# AnyFC_Final.net
KiCad netlist of a schematic drawn in EAGLE
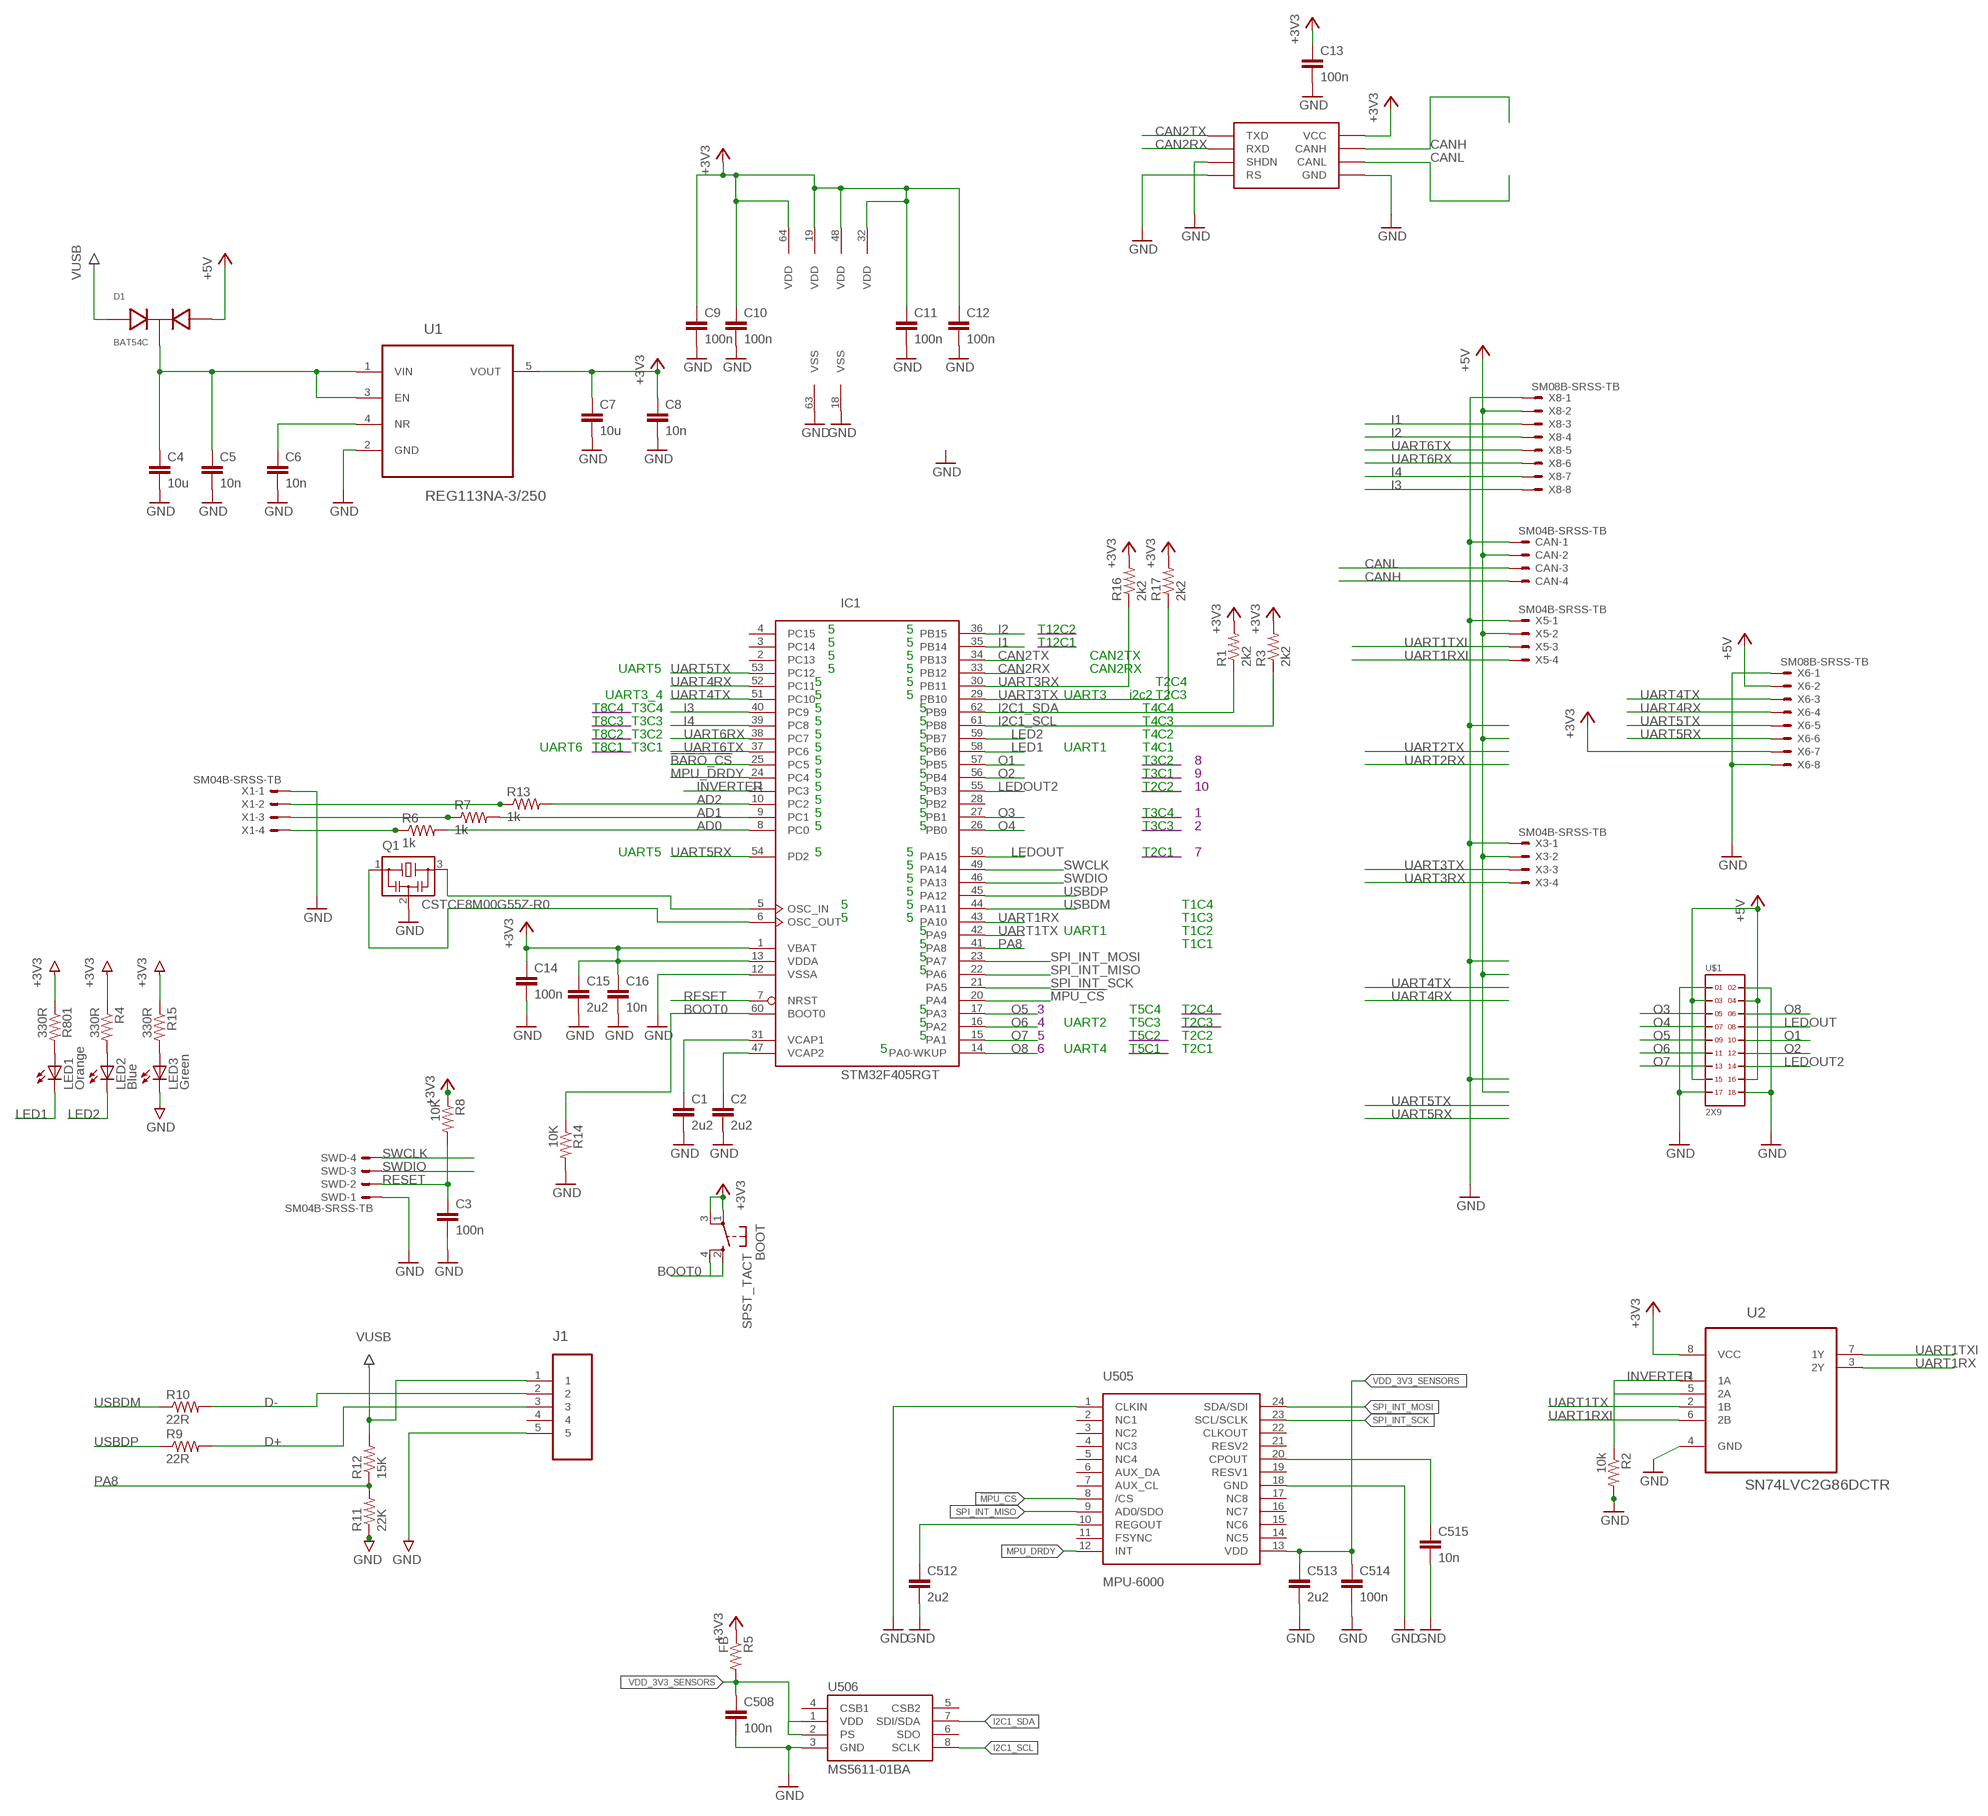
[diagram p0: schematic, sheet 1]

(export (version "E")
  (design (tool "Eeschema 10.0.6"))
  (components
    (comp (ref "BOOT")
      (value "SPST_TACT")
      (footprint "eagle-import:EVQ-PU")
      (libsource (lib "eagle-import") (part "SPST_TACT"))
    )
    (comp (ref "C1")
      (value "2u2")
      (footprint "eagle-import:0603-CAP")
      (fields (field (name "PARTNO") "C1608X6S1C225K080AC"))
      (libsource (lib "eagle-import") (part "CAP0603"))
    )
    (comp (ref "C2")
      (value "2u2")
      (footprint "eagle-import:0603-CAP")
      (fields (field (name "PARTNO") "C1608X6S1C225K080AC"))
      (libsource (lib "eagle-import") (part "CAP0603"))
    )
    (comp (ref "C3")
      (value "100n")
      (footprint "eagle-import:0402-CAP")
      (fields (field (name "PARTNO") "C1608X6S1C225K080AC"))
      (libsource (lib "eagle-import") (part "CAP0402"))
    )
    (comp (ref "C4")
      (value "10u")
      (footprint "eagle-import:0805-CAP")
      (fields (field (name "PARTNO") "C1608X6S1C225K080AC"))
      (libsource (lib "eagle-import") (part "CAP0805"))
    )
    (comp (ref "C5")
      (value "10n")
      (footprint "eagle-import:0402-CAP")
      (fields (field (name "PARTNO") "C1608X6S1C225K080AC"))
      (libsource (lib "eagle-import") (part "CAP0402"))
    )
    (comp (ref "C6")
      (value "10n")
      (footprint "eagle-import:0402-CAP")
      (fields (field (name "PARTNO") "C1608X6S1C225K080AC"))
      (libsource (lib "eagle-import") (part "CAP0402"))
    )
    (comp (ref "C7")
      (value "10u")
      (footprint "eagle-import:0805-CAP")
      (fields (field (name "PARTNO") "C1608X6S1C225K080AC"))
      (libsource (lib "eagle-import") (part "CAP0805"))
    )
    (comp (ref "C8")
      (value "10n")
      (footprint "eagle-import:0402-CAP")
      (fields (field (name "PARTNO") "C1608X6S1C225K080AC"))
      (libsource (lib "eagle-import") (part "CAP0402"))
    )
    (comp (ref "C9")
      (value "100n")
      (footprint "eagle-import:0402-CAP")
      (fields (field (name "PARTNO") "C1608X6S1C225K080AC"))
      (libsource (lib "eagle-import") (part "CAP0402"))
    )
    (comp (ref "C10")
      (value "100n")
      (footprint "eagle-import:0402-CAP")
      (fields (field (name "PARTNO") "C1608X6S1C225K080AC"))
      (libsource (lib "eagle-import") (part "CAP0402"))
    )
    (comp (ref "C11")
      (value "100n")
      (footprint "eagle-import:0402-CAP")
      (fields (field (name "PARTNO") "C1608X6S1C225K080AC"))
      (libsource (lib "eagle-import") (part "CAP0402"))
    )
    (comp (ref "C12")
      (value "100n")
      (footprint "eagle-import:0402-CAP")
      (fields (field (name "PARTNO") "C1608X6S1C225K080AC"))
      (libsource (lib "eagle-import") (part "CAP0402"))
    )
    (comp (ref "C13")
      (value "100n")
      (footprint "eagle-import:0402-CAP")
      (fields (field (name "PARTNO") "C1608X6S1C225K080AC"))
      (libsource (lib "eagle-import") (part "CAP0402"))
    )
    (comp (ref "C14")
      (value "100n")
      (footprint "eagle-import:0402-CAP")
      (fields (field (name "PARTNO") "C1608X6S1C225K080AC"))
      (libsource (lib "eagle-import") (part "CAP0402"))
    )
    (comp (ref "C15")
      (value "2u2")
      (footprint "eagle-import:0603-CAP")
      (fields (field (name "PARTNO") "C1608X6S1C225K080AC"))
      (libsource (lib "eagle-import") (part "CAP0603"))
    )
    (comp (ref "C16")
      (value "10n")
      (footprint "eagle-import:0402-CAP")
      (fields (field (name "PARTNO") "C1608X6S1C225K080AC"))
      (libsource (lib "eagle-import") (part "CAP0402"))
    )
    (comp (ref "C508")
      (value "100n")
      (footprint "eagle-import:0402-CAP")
      (fields (field (name "PARTNO") "CC0402ZRY5V7BB104"))
      (libsource (lib "eagle-import") (part "CAP0402"))
    )
    (comp (ref "C512")
      (value "2u2")
      (footprint "eagle-import:0603-CAP")
      (fields (field (name "PARTNO") "C1608X6S1C225K080AC"))
      (libsource (lib "eagle-import") (part "CAP0603"))
    )
    (comp (ref "C513")
      (value "2u2")
      (footprint "eagle-import:0603-CAP")
      (fields (field (name "PARTNO") "C1608X6S1C225K080AC"))
      (libsource (lib "eagle-import") (part "CAP0603"))
    )
    (comp (ref "C514")
      (value "100n")
      (footprint "eagle-import:0402-CAP")
      (fields (field (name "PARTNO") "CC0402ZRY5V7BB104"))
      (libsource (lib "eagle-import") (part "CAP0402"))
    )
    (comp (ref "C515")
      (value "10n")
      (footprint "eagle-import:0402-CAP")
      (fields (field (name "PARTNO") "06033C103JAT2A"))
      (libsource (lib "eagle-import") (part "CAP0402"))
    )
    (comp (ref "CAN")
      (value "SM04B-SRSS-TB")
      (footprint "eagle-import:SM04B-SRSS-TB")
      (libsource (lib "eagle-import") (part "?M04B-SRSS-TBS"))
    )
    (comp (ref "D1")
      (value "BAT54C")
      (footprint "eagle-import:SOT23")
      (libsource (lib "eagle-import") (part "BAT54C"))
    )
    (comp (ref "IC1")
      (value "STM32F405RGT")
      (footprint "eagle-import:LQFP64")
      (libsource (lib "eagle-import") (part "STM32F405RTG"))
    )
    (comp (ref "J1")
      (value "47346-0001")
      (footprint "eagle-import:MOLEX_47346-0001")
      (libsource (lib "eagle-import") (part "47346-0001"))
    )
    (comp (ref "LED1")
      (value "Orange")
      (footprint "eagle-import:CHIPLED_0603")
      (libsource (lib "eagle-import") (part "LEDCHIPLED_0603"))
    )
    (comp (ref "LED2")
      (value "Blue")
      (footprint "eagle-import:CHIPLED_0603")
      (libsource (lib "eagle-import") (part "LEDCHIPLED_0603"))
    )
    (comp (ref "LED3")
      (value "Green")
      (footprint "eagle-import:CHIPLED_0603")
      (libsource (lib "eagle-import") (part "LEDCHIPLED_0603"))
    )
    (comp (ref "Q1")
      (value "CSTCE8M00G55Z-R0")
      (footprint "eagle-import:CSTER12M")
      (fields (field (name "MPN") "CSTCC12M0"))
      (libsource (lib "eagle-import") (part "CSTCR6M00G53Z"))
    )
    (comp (ref "R1")
      (value "2k2")
      (footprint "eagle-import:0402-RES")
      (fields (field (name "PARTNO") "RC0402FR-0710KL"))
      (libsource (lib "eagle-import") (part "RESISTOR0402-RES"))
    )
    (comp (ref "R2")
      (value "10k")
      (footprint "eagle-import:0402-RES")
      (fields (field (name "PARTNO") "RC0402FR-0710KL"))
      (libsource (lib "eagle-import") (part "RESISTOR0402-RES"))
    )
    (comp (ref "R3")
      (value "2k2")
      (footprint "eagle-import:0402-RES")
      (fields (field (name "PARTNO") "RC0402FR-0710KL"))
      (libsource (lib "eagle-import") (part "RESISTOR0402-RES"))
    )
    (comp (ref "R4")
      (value "330R")
      (footprint "eagle-import:0402-RES")
      (fields (field (name "PARTNO") "RC0402FR-0710KL"))
      (libsource (lib "eagle-import") (part "RESISTOR0402-RES"))
    )
    (comp (ref "R5")
      (value "FB")
      (footprint "eagle-import:0603-RES")
      (fields (field (name "PARTNO") "RC0402FR-0710KL"))
      (libsource (lib "eagle-import") (part "RESISTOR0603-RES"))
    )
    (comp (ref "R6")
      (value "1k")
      (footprint "eagle-import:0402-RES")
      (fields (field (name "PARTNO") "RC0402FR-0710KL"))
      (libsource (lib "eagle-import") (part "RESISTOR0402-RES"))
    )
    (comp (ref "R7")
      (value "1k")
      (footprint "eagle-import:0402-RES")
      (fields (field (name "PARTNO") "RC0402FR-0710KL"))
      (libsource (lib "eagle-import") (part "RESISTOR0402-RES"))
    )
    (comp (ref "R8")
      (value "10K")
      (footprint "eagle-import:0402-RES")
      (fields (field (name "PARTNO") "RC0402FR-0710KL"))
      (libsource (lib "eagle-import") (part "RESISTOR0402-RES"))
    )
    (comp (ref "R9")
      (value "22R")
      (footprint "eagle-import:0402-RES")
      (fields (field (name "PARTNO") "RC0402FR-0710KL"))
      (libsource (lib "eagle-import") (part "RESISTOR0402-RES"))
    )
    (comp (ref "R10")
      (value "22R")
      (footprint "eagle-import:0402-RES")
      (fields (field (name "PARTNO") "RC0402FR-0710KL"))
      (libsource (lib "eagle-import") (part "RESISTOR0402-RES"))
    )
    (comp (ref "R11")
      (value "22K")
      (footprint "eagle-import:0402-RES")
      (fields (field (name "PARTNO") "RC0402FR-0710KL"))
      (libsource (lib "eagle-import") (part "RESISTOR0402-RES"))
    )
    (comp (ref "R12")
      (value "15K")
      (footprint "eagle-import:0402-RES")
      (fields (field (name "PARTNO") "RC0402FR-0710KL"))
      (libsource (lib "eagle-import") (part "RESISTOR0402-RES"))
    )
    (comp (ref "R13")
      (value "1k")
      (footprint "eagle-import:0402-RES")
      (fields (field (name "PARTNO") "RC0402FR-0710KL"))
      (libsource (lib "eagle-import") (part "RESISTOR0402-RES"))
    )
    (comp (ref "R14")
      (value "10K")
      (footprint "eagle-import:0402-RES")
      (fields (field (name "PARTNO") "RC0402FR-0710KL"))
      (libsource (lib "eagle-import") (part "RESISTOR0402-RES"))
    )
    (comp (ref "R15")
      (value "330R")
      (footprint "eagle-import:0402-RES")
      (fields (field (name "PARTNO") "RC0402FR-0710KL"))
      (libsource (lib "eagle-import") (part "RESISTOR0402-RES"))
    )
    (comp (ref "R16")
      (value "2k2")
      (footprint "eagle-import:0402-RES")
      (fields (field (name "PARTNO") "RC0402FR-0710KL"))
      (libsource (lib "eagle-import") (part "RESISTOR0402-RES"))
    )
    (comp (ref "R17")
      (value "2k2")
      (footprint "eagle-import:0402-RES")
      (fields (field (name "PARTNO") "RC0402FR-0710KL"))
      (libsource (lib "eagle-import") (part "RESISTOR0402-RES"))
    )
    (comp (ref "R801")
      (value "330R")
      (footprint "eagle-import:0402-RES")
      (fields (field (name "PARTNO") "RC0402FR-0710KL"))
      (libsource (lib "eagle-import") (part "RESISTOR0402-RES"))
    )
    (comp (ref "SWD")
      (value "SM04B-SRSS-TB")
      (footprint "eagle-import:SM04B-SRSS-TB")
      (libsource (lib "eagle-import") (part "?M04B-SRSS-TBS"))
    )
    (comp (ref "U$1")
      (value "2X9")
      (footprint "eagle-import:2X9")
      (libsource (lib "eagle-import") (part "2X9"))
    )
    (comp (ref "U1")
      (value "REG113NA-3/250")
      (footprint "eagle-import:SOT95P280X145-5N")
      (libsource (lib "eagle-import") (part "REG113NA-3/250"))
    )
    (comp (ref "U2")
      (value "SN74LVC2G86DCTR")
      (footprint "eagle-import:SOP65P400X130-8N")
      (libsource (lib "eagle-import") (part "SN74LVC2G86DCTR"))
    )
    (comp (ref "U3")
      (value "MAX3051EKA")
      (footprint "eagle-import:SOT23-8L")
      (libsource (lib "eagle-import") (part "MAX3051EKA"))
    )
    (comp (ref "U505")
      (value "MPU-6000")
      (footprint "eagle-import:QFN-24")
      (libsource (lib "eagle-import") (part "MPU-6000"))
    )
    (comp (ref "U506")
      (value "MS5611-01BA")
      (footprint "eagle-import:MS5611-01BA")
      (libsource (lib "eagle-import") (part "MS5611-01BA"))
    )
    (comp (ref "X1")
      (value "SM04B-SRSS-TB")
      (footprint "eagle-import:SM04B-SRSS-TB")
      (libsource (lib "eagle-import") (part "?M04B-SRSS-TBS"))
    )
    (comp (ref "X3")
      (value "SM04B-SRSS-TB")
      (footprint "eagle-import:SM04B-SRSS-TB")
      (libsource (lib "eagle-import") (part "?M04B-SRSS-TBS"))
    )
    (comp (ref "X5")
      (value "SM04B-SRSS-TB")
      (footprint "eagle-import:SM04B-SRSS-TB")
      (libsource (lib "eagle-import") (part "?M04B-SRSS-TBS"))
    )
    (comp (ref "X6")
      (value "SM08B-SRSS-TB")
      (footprint "eagle-import:SM08B-SRSS-TB")
      (libsource (lib "eagle-import") (part "?M08B-SRSS-TBS"))
    )
    (comp (ref "X8")
      (value "SM08B-SRSS-TB")
      (footprint "eagle-import:SM08B-SRSS-TB")
      (libsource (lib "eagle-import") (part "?M08B-SRSS-TBS"))
    )
  )
  (nets
    (net (code "1") (name "+3V3") (class "Default")
      (node (ref "BOOT") (pin "1") (pinfunction "P_1") (pintype "passive"))
      (node (ref "BOOT") (pin "3") (pinfunction "P1_3") (pintype "passive"))
      (node (ref "C10") (pin "P$1") (pinfunction "1_P$1") (pintype "passive"))
      (node (ref "C11") (pin "P$1") (pinfunction "1_P$1") (pintype "passive"))
      (node (ref "C12") (pin "P$1") (pinfunction "1_P$1") (pintype "passive"))
      (node (ref "C13") (pin "P$1") (pinfunction "1_P$1") (pintype "passive"))
      (node (ref "C14") (pin "P$1") (pinfunction "1_P$1") (pintype "passive"))
      (node (ref "C15") (pin "P$1") (pinfunction "1_P$1") (pintype "passive"))
      (node (ref "C16") (pin "P$1") (pinfunction "1_P$1") (pintype "passive"))
      (node (ref "C7") (pin "P$1") (pinfunction "1_P$1") (pintype "passive"))
      (node (ref "C8") (pin "P$1") (pinfunction "1_P$1") (pintype "passive"))
      (node (ref "C9") (pin "P$1") (pinfunction "1_P$1") (pintype "passive"))
      (node (ref "IC1") (pin "1") (pinfunction "VBAT_1") (pintype "power_in"))
      (node (ref "IC1") (pin "13") (pinfunction "VDDA_13") (pintype "power_in"))
      (node (ref "IC1") (pin "19") (pinfunction "VDD_19") (pintype "power_in"))
      (node (ref "IC1") (pin "32") (pinfunction "VDD_32") (pintype "power_in"))
      (node (ref "IC1") (pin "48") (pinfunction "VDD_48") (pintype "power_in"))
      (node (ref "IC1") (pin "64") (pinfunction "VDD_64") (pintype "power_in"))
      (node (ref "R1") (pin "P$2") (pinfunction "2_P$2") (pintype "passive"))
      (node (ref "R15") (pin "P$1") (pinfunction "1_P$1") (pintype "passive"))
      (node (ref "R16") (pin "P$2") (pinfunction "2_P$2") (pintype "passive"))
      (node (ref "R17") (pin "P$2") (pinfunction "2_P$2") (pintype "passive"))
      (node (ref "R3") (pin "P$2") (pinfunction "2_P$2") (pintype "passive"))
      (node (ref "R4") (pin "P$1") (pinfunction "1_P$1") (pintype "passive"))
      (node (ref "R5") (pin "1") (pinfunction "1_1") (pintype "passive"))
      (node (ref "R8") (pin "P$1") (pinfunction "1_P$1") (pintype "passive"))
      (node (ref "R801") (pin "P$1") (pinfunction "1_P$1") (pintype "passive"))
      (node (ref "U1") (pin "5") (pinfunction "VOUT_5") (pintype "output"))
      (node (ref "U2") (pin "8") (pinfunction "VCC_8") (pintype "power_in"))
      (node (ref "U3") (pin "3") (pinfunction "VCC_3") (pintype "bidirectional"))
      (node (ref "X6") (pin "7") (pinfunction "S_7") (pintype "passive"))
    )
    (net (code "2") (name "+5V") (class "Default")
      (node (ref "CAN") (pin "2") (pinfunction "S_2") (pintype "passive"))
      (node (ref "D1") (pin "2") (pinfunction "P$2_2") (pintype "input"))
      (node (ref "U$1") (pin "15") (pinfunction "15_15") (pintype "bidirectional"))
      (node (ref "U$1") (pin "16") (pinfunction "16_16") (pintype "bidirectional"))
      (node (ref "U$1") (pin "3") (pinfunction "3_3") (pintype "bidirectional"))
      (node (ref "U$1") (pin "4") (pinfunction "4_4") (pintype "bidirectional"))
      (node (ref "X3") (pin "2") (pinfunction "S_2") (pintype "passive"))
      (node (ref "X5") (pin "2") (pinfunction "S_2") (pintype "passive"))
      (node (ref "X6") (pin "2") (pinfunction "S_2") (pintype "passive"))
      (node (ref "X8") (pin "2") (pinfunction "S_2") (pintype "passive"))
    )
    (net (code "3") (name "/AD0") (class "Default")
      (node (ref "IC1") (pin "8") (pinfunction "PC0_8") (pintype "bidirectional"))
      (node (ref "R6") (pin "P$2") (pinfunction "2_P$2") (pintype "passive"))
    )
    (net (code "4") (name "/AD1") (class "Default")
      (node (ref "IC1") (pin "9") (pinfunction "PC1_9") (pintype "bidirectional"))
      (node (ref "R7") (pin "P$2") (pinfunction "2_P$2") (pintype "passive"))
    )
    (net (code "5") (name "/AD2") (class "Default")
      (node (ref "IC1") (pin "10") (pinfunction "PC2_10") (pintype "bidirectional"))
      (node (ref "R13") (pin "P$2") (pinfunction "2_P$2") (pintype "passive"))
    )
    (net (code "6") (name "/BOOT0") (class "Default")
      (node (ref "BOOT") (pin "2") (pinfunction "S_2") (pintype "passive"))
      (node (ref "BOOT") (pin "4") (pinfunction "S1_4") (pintype "passive"))
      (node (ref "IC1") (pin "60") (pinfunction "BOOT0_60") (pintype "input"))
      (node (ref "R14") (pin "P$1") (pinfunction "1_P$1") (pintype "passive"))
    )
    (net (code "7") (name "/CAN2RX") (class "Default")
      (node (ref "IC1") (pin "33") (pinfunction "PB12_33") (pintype "bidirectional"))
      (node (ref "U3") (pin "4") (pinfunction "RXD_4") (pintype "bidirectional"))
    )
    (net (code "8") (name "/CAN2TX") (class "Default")
      (node (ref "IC1") (pin "34") (pinfunction "PB13_34") (pintype "bidirectional"))
      (node (ref "U3") (pin "1") (pinfunction "TXD_1") (pintype "bidirectional"))
    )
    (net (code "9") (name "/CANH") (class "Default")
      (node (ref "CAN") (pin "4") (pinfunction "S_4") (pintype "passive"))
      (node (ref "U3") (pin "7") (pinfunction "CANH_7") (pintype "bidirectional"))
    )
    (net (code "10") (name "/CANL") (class "Default")
      (node (ref "CAN") (pin "3") (pinfunction "S_3") (pintype "passive"))
      (node (ref "U3") (pin "6") (pinfunction "CANL_6") (pintype "bidirectional"))
    )
    (net (code "11") (name "/D+") (class "Default")
      (node (ref "J1") (pin "3") (pinfunction "3_3") (pintype "input"))
      (node (ref "R9") (pin "P$2") (pinfunction "2_P$2") (pintype "passive"))
    )
    (net (code "12") (name "/D-") (class "Default")
      (node (ref "J1") (pin "2") (pinfunction "2_2") (pintype "input"))
      (node (ref "R10") (pin "P$2") (pinfunction "2_P$2") (pintype "passive"))
    )
    (net (code "13") (name "/I1") (class "Default")
      (node (ref "IC1") (pin "35") (pinfunction "PB14_35") (pintype "bidirectional"))
      (node (ref "X8") (pin "3") (pinfunction "S_3") (pintype "passive"))
    )
    (net (code "14") (name "/I2") (class "Default")
      (node (ref "IC1") (pin "36") (pinfunction "PB15_36") (pintype "bidirectional"))
      (node (ref "X8") (pin "4") (pinfunction "S_4") (pintype "passive"))
    )
    (net (code "15") (name "/I3") (class "Default")
      (node (ref "IC1") (pin "40") (pinfunction "PC9_40") (pintype "bidirectional"))
      (node (ref "X8") (pin "8") (pinfunction "S_8") (pintype "passive"))
    )
    (net (code "16") (name "/I4") (class "Default")
      (node (ref "IC1") (pin "39") (pinfunction "PC8_39") (pintype "bidirectional"))
      (node (ref "X8") (pin "7") (pinfunction "S_7") (pintype "passive"))
    )
    (net (code "17") (name "/INVERTER") (class "Default")
      (node (ref "IC1") (pin "11") (pinfunction "PC3_11") (pintype "bidirectional"))
      (node (ref "R2") (pin "P$1") (pinfunction "1_P$1") (pintype "passive"))
      (node (ref "U2") (pin "1") (pinfunction "1A_1") (pintype "input"))
      (node (ref "U2") (pin "5") (pinfunction "2A_5") (pintype "input"))
    )
    (net (code "18") (name "/LED1") (class "Default")
      (node (ref "IC1") (pin "58") (pinfunction "PB6_58") (pintype "bidirectional"))
      (node (ref "LED1") (pin "C") (pinfunction "C_C") (pintype "passive"))
    )
    (net (code "19") (name "/LED2") (class "Default")
      (node (ref "IC1") (pin "59") (pinfunction "PB7_59") (pintype "bidirectional"))
      (node (ref "LED2") (pin "C") (pinfunction "C_C") (pintype "passive"))
    )
    (net (code "20") (name "/LEDOUT") (class "Default")
      (node (ref "IC1") (pin "50") (pinfunction "PA15_50") (pintype "bidirectional"))
      (node (ref "U$1") (pin "8") (pinfunction "8_8") (pintype "bidirectional"))
    )
    (net (code "21") (name "/LEDOUT2") (class "Default")
      (node (ref "IC1") (pin "55") (pinfunction "PB3_55") (pintype "bidirectional"))
      (node (ref "U$1") (pin "14") (pinfunction "14_14") (pintype "bidirectional"))
    )
    (net (code "22") (name "/O1") (class "Default")
      (node (ref "IC1") (pin "57") (pinfunction "PB5_57") (pintype "bidirectional"))
      (node (ref "U$1") (pin "10") (pinfunction "10_10") (pintype "bidirectional"))
    )
    (net (code "23") (name "/O2") (class "Default")
      (node (ref "IC1") (pin "56") (pinfunction "PB4_56") (pintype "bidirectional"))
      (node (ref "U$1") (pin "12") (pinfunction "12_12") (pintype "bidirectional"))
    )
    (net (code "24") (name "/O3") (class "Default")
      (node (ref "IC1") (pin "27") (pinfunction "PB1_27") (pintype "bidirectional"))
      (node (ref "U$1") (pin "5") (pinfunction "5_5") (pintype "bidirectional"))
    )
    (net (code "25") (name "/O4") (class "Default")
      (node (ref "IC1") (pin "26") (pinfunction "PB0_26") (pintype "bidirectional"))
      (node (ref "U$1") (pin "7") (pinfunction "7_7") (pintype "bidirectional"))
    )
    (net (code "26") (name "/O5") (class "Default")
      (node (ref "IC1") (pin "17") (pinfunction "PA3_17") (pintype "bidirectional"))
      (node (ref "U$1") (pin "9") (pinfunction "9_9") (pintype "bidirectional"))
    )
    (net (code "27") (name "/O6") (class "Default")
      (node (ref "IC1") (pin "16") (pinfunction "PA2_16") (pintype "bidirectional"))
      (node (ref "U$1") (pin "11") (pinfunction "11_11") (pintype "bidirectional"))
    )
    (net (code "28") (name "/O7") (class "Default")
      (node (ref "IC1") (pin "15") (pinfunction "PA1_15") (pintype "bidirectional"))
      (node (ref "U$1") (pin "13") (pinfunction "13_13") (pintype "bidirectional"))
    )
    (net (code "29") (name "/O8") (class "Default")
      (node (ref "IC1") (pin "14") (pinfunction "PA0-WKUP_14") (pintype "bidirectional"))
      (node (ref "U$1") (pin "6") (pinfunction "6_6") (pintype "bidirectional"))
    )
    (net (code "30") (name "/PA8") (class "Default")
      (node (ref "IC1") (pin "41") (pinfunction "PA8_41") (pintype "bidirectional"))
      (node (ref "R11") (pin "P$2") (pinfunction "2_P$2") (pintype "passive"))
      (node (ref "R12") (pin "P$1") (pinfunction "1_P$1") (pintype "passive"))
    )
    (net (code "31") (name "/RESET") (class "Default")
      (node (ref "C3") (pin "P$1") (pinfunction "1_P$1") (pintype "passive"))
      (node (ref "IC1") (pin "7") (pinfunction "NRST_7") (pintype "bidirectional"))
      (node (ref "R8") (pin "P$2") (pinfunction "2_P$2") (pintype "passive"))
      (node (ref "SWD") (pin "2") (pinfunction "S_2") (pintype "passive"))
    )
    (net (code "32") (name "/SWCLK") (class "Default")
      (node (ref "IC1") (pin "49") (pinfunction "PA14_49") (pintype "bidirectional"))
      (node (ref "SWD") (pin "4") (pinfunction "S_4") (pintype "passive"))
    )
    (net (code "33") (name "/SWDIO") (class "Default")
      (node (ref "IC1") (pin "46") (pinfunction "PA13_46") (pintype "bidirectional"))
      (node (ref "SWD") (pin "3") (pinfunction "S_3") (pintype "passive"))
    )
    (net (code "34") (name "/UART1RX") (class "Default")
      (node (ref "IC1") (pin "43") (pinfunction "PA10_43") (pintype "bidirectional"))
      (node (ref "U2") (pin "3") (pinfunction "2Y_3") (pintype "output"))
    )
    (net (code "35") (name "/UART1RXI") (class "Default")
      (node (ref "U2") (pin "6") (pinfunction "2B_6") (pintype "input"))
      (node (ref "X5") (pin "4") (pinfunction "S_4") (pintype "passive"))
    )
    (net (code "36") (name "/UART1TX") (class "Default")
      (node (ref "IC1") (pin "42") (pinfunction "PA9_42") (pintype "bidirectional"))
      (node (ref "U2") (pin "2") (pinfunction "1B_2") (pintype "input"))
    )
    (net (code "37") (name "/UART1TXI") (class "Default")
      (node (ref "U2") (pin "7") (pinfunction "1Y_7") (pintype "output"))
      (node (ref "X5") (pin "3") (pinfunction "S_3") (pintype "passive"))
    )
    (net (code "40") (name "/UART3RX") (class "Default")
      (node (ref "IC1") (pin "30") (pinfunction "PB11_30") (pintype "bidirectional"))
      (node (ref "R16") (pin "P$1") (pinfunction "1_P$1") (pintype "passive"))
      (node (ref "X3") (pin "4") (pinfunction "S_4") (pintype "passive"))
    )
    (net (code "41") (name "/UART3TX") (class "Default")
      (node (ref "IC1") (pin "29") (pinfunction "PB10_29") (pintype "bidirectional"))
      (node (ref "R17") (pin "P$1") (pinfunction "1_P$1") (pintype "passive"))
      (node (ref "X3") (pin "3") (pinfunction "S_3") (pintype "passive"))
    )
    (net (code "42") (name "/UART4RX") (class "Default")
      (node (ref "IC1") (pin "52") (pinfunction "PC11_52") (pintype "bidirectional"))
      (node (ref "X6") (pin "4") (pinfunction "S_4") (pintype "passive"))
    )
    (net (code "43") (name "/UART4TX") (class "Default")
      (node (ref "IC1") (pin "51") (pinfunction "PC10_51") (pintype "bidirectional"))
      (node (ref "X6") (pin "3") (pinfunction "S_3") (pintype "passive"))
    )
    (net (code "44") (name "/UART5RX") (class "Default")
      (node (ref "IC1") (pin "54") (pinfunction "PD2_54") (pintype "bidirectional"))
      (node (ref "X6") (pin "6") (pinfunction "S_6") (pintype "passive"))
    )
    (net (code "45") (name "/UART5TX") (class "Default")
      (node (ref "IC1") (pin "53") (pinfunction "PC12_53") (pintype "bidirectional"))
      (node (ref "X6") (pin "5") (pinfunction "S_5") (pintype "passive"))
    )
    (net (code "46") (name "/UART6RX") (class "Default")
      (node (ref "IC1") (pin "38") (pinfunction "PC7_38") (pintype "bidirectional"))
      (node (ref "X8") (pin "6") (pinfunction "S_6") (pintype "passive"))
    )
    (net (code "47") (name "/UART6TX") (class "Default")
      (node (ref "IC1") (pin "37") (pinfunction "PC6_37") (pintype "bidirectional"))
      (node (ref "X8") (pin "5") (pinfunction "S_5") (pintype "passive"))
    )
    (net (code "48") (name "/USBDM") (class "Default")
      (node (ref "IC1") (pin "44") (pinfunction "PA11_44") (pintype "bidirectional"))
      (node (ref "R10") (pin "P$1") (pinfunction "1_P$1") (pintype "passive"))
    )
    (net (code "49") (name "/USBDP") (class "Default")
      (node (ref "IC1") (pin "45") (pinfunction "PA12_45") (pintype "bidirectional"))
      (node (ref "R9") (pin "P$1") (pinfunction "1_P$1") (pintype "passive"))
    )
    (net (code "50") (name "/VUSB") (class "Default")
      (node (ref "D1") (pin "1") (pinfunction "P$1_1") (pintype "input"))
      (node (ref "J1") (pin "1") (pinfunction "1_1") (pintype "input"))
      (node (ref "R12") (pin "P$2") (pinfunction "2_P$2") (pintype "passive"))
    )
    (net (code "51") (name "/~{BARO_CS}") (class "Default")
      (node (ref "IC1") (pin "25") (pinfunction "PC5_25") (pintype "bidirectional"))
    )
    (net (code "52") (name "/~{MPU_CS}") (class "Default")
      (node (ref "IC1") (pin "20") (pinfunction "PA4_20") (pintype "bidirectional"))
      (node (ref "U505") (pin "8") (pinfunction "/CS_8") (pintype "bidirectional"))
    )
    (net (code "53") (name "GND") (class "Default")
      (node (ref "C1") (pin "P$2") (pinfunction "2_P$2") (pintype "passive"))
      (node (ref "C10") (pin "P$2") (pinfunction "2_P$2") (pintype "passive"))
      (node (ref "C11") (pin "P$2") (pinfunction "2_P$2") (pintype "passive"))
      (node (ref "C12") (pin "P$2") (pinfunction "2_P$2") (pintype "passive"))
      (node (ref "C13") (pin "P$2") (pinfunction "2_P$2") (pintype "passive"))
      (node (ref "C14") (pin "P$2") (pinfunction "2_P$2") (pintype "passive"))
      (node (ref "C15") (pin "P$2") (pinfunction "2_P$2") (pintype "passive"))
      (node (ref "C16") (pin "P$2") (pinfunction "2_P$2") (pintype "passive"))
      (node (ref "C2") (pin "P$2") (pinfunction "2_P$2") (pintype "passive"))
      (node (ref "C3") (pin "P$2") (pinfunction "2_P$2") (pintype "passive"))
      (node (ref "C4") (pin "P$2") (pinfunction "2_P$2") (pintype "passive"))
      (node (ref "C5") (pin "P$2") (pinfunction "2_P$2") (pintype "passive"))
      (node (ref "C508") (pin "P$2") (pinfunction "2_P$2") (pintype "passive"))
      (node (ref "C512") (pin "P$2") (pinfunction "2_P$2") (pintype "passive"))
      (node (ref "C513") (pin "P$2") (pinfunction "2_P$2") (pintype "passive"))
      (node (ref "C514") (pin "P$2") (pinfunction "2_P$2") (pintype "passive"))
      (node (ref "C515") (pin "P$2") (pinfunction "2_P$2") (pintype "passive"))
      (node (ref "C6") (pin "P$2") (pinfunction "2_P$2") (pintype "passive"))
      (node (ref "C7") (pin "P$2") (pinfunction "2_P$2") (pintype "passive"))
      (node (ref "C8") (pin "P$2") (pinfunction "2_P$2") (pintype "passive"))
      (node (ref "C9") (pin "P$2") (pinfunction "2_P$2") (pintype "passive"))
      (node (ref "CAN") (pin "1") (pinfunction "S_1") (pintype "passive"))
      (node (ref "IC1") (pin "12") (pinfunction "VSSA_12") (pintype "power_in"))
      (node (ref "IC1") (pin "18") (pinfunction "VSS_18") (pintype "power_in"))
      (node (ref "IC1") (pin "63") (pinfunction "VSS_63") (pintype "power_in"))
      (node (ref "J1") (pin "5") (pinfunction "5_5") (pintype "input"))
      (node (ref "LED3") (pin "C") (pinfunction "C_C") (pintype "passive"))
      (node (ref "Q1") (pin "2") (pinfunction "2_2") (pintype "passive"))
      (node (ref "R11") (pin "P$1") (pinfunction "1_P$1") (pintype "passive"))
      (node (ref "R14") (pin "P$2") (pinfunction "2_P$2") (pintype "passive"))
      (node (ref "R2") (pin "P$2") (pinfunction "2_P$2") (pintype "passive"))
      (node (ref "SWD") (pin "1") (pinfunction "S_1") (pintype "passive"))
      (node (ref "U$1") (pin "1") (pinfunction "1_1") (pintype "bidirectional"))
      (node (ref "U$1") (pin "17") (pinfunction "17_17") (pintype "bidirectional"))
      (node (ref "U$1") (pin "18") (pinfunction "18_18") (pintype "bidirectional"))
      (node (ref "U$1") (pin "2") (pinfunction "2_2") (pintype "bidirectional"))
      (node (ref "U1") (pin "2") (pinfunction "GND_2") (pintype "passive"))
      (node (ref "U2") (pin "4") (pinfunction "GND_4") (pintype "passive"))
      (node (ref "U3") (pin "2") (pinfunction "GND_2") (pintype "bidirectional"))
      (node (ref "U3") (pin "5") (pinfunction "SHDN_5") (pintype "bidirectional"))
      (node (ref "U3") (pin "8") (pinfunction "RS_8") (pintype "bidirectional"))
      (node (ref "U505") (pin "1") (pinfunction "CLKIN_1") (pintype "bidirectional"))
      (node (ref "U505") (pin "18") (pinfunction "GND_18") (pintype "bidirectional"))
      (node (ref "U506") (pin "3") (pinfunction "GND_3") (pintype "bidirectional"))
      (node (ref "X1") (pin "1") (pinfunction "S_1") (pintype "passive"))
      (node (ref "X3") (pin "1") (pinfunction "S_1") (pintype "passive"))
      (node (ref "X5") (pin "1") (pinfunction "S_1") (pintype "passive"))
      (node (ref "X6") (pin "1") (pinfunction "S_1") (pintype "passive"))
      (node (ref "X6") (pin "8") (pinfunction "S_8") (pintype "passive"))
      (node (ref "X8") (pin "1") (pinfunction "S_1") (pintype "passive"))
    )
    (net (code "54") (name "I2C1_SCL") (class "Default")
      (node (ref "IC1") (pin "61") (pinfunction "PB8_61") (pintype "bidirectional"))
      (node (ref "R3") (pin "P$1") (pinfunction "1_P$1") (pintype "passive"))
      (node (ref "U506") (pin "8") (pinfunction "SCLK_8") (pintype "bidirectional"))
    )
    (net (code "55") (name "I2C1_SDA") (class "Default")
      (node (ref "IC1") (pin "62") (pinfunction "PB9_62") (pintype "bidirectional"))
      (node (ref "R1") (pin "P$1") (pinfunction "1_P$1") (pintype "passive"))
      (node (ref "U506") (pin "7") (pinfunction "SDI/SDA_7") (pintype "bidirectional"))
    )
    (net (code "56") (name "MPU_DRDY") (class "Default")
      (node (ref "IC1") (pin "24") (pinfunction "PC4_24") (pintype "bidirectional"))
      (node (ref "U505") (pin "12") (pinfunction "INT_12") (pintype "bidirectional"))
    )
    (net (code "57") (name "Net-(C1-1)") (class "Default")
      (node (ref "C1") (pin "P$1") (pinfunction "1_P$1") (pintype "passive"))
      (node (ref "IC1") (pin "31") (pinfunction "VCAP1_31") (pintype "power_in"))
    )
    (net (code "58") (name "Net-(C2-1)") (class "Default")
      (node (ref "C2") (pin "P$1") (pinfunction "1_P$1") (pintype "passive"))
      (node (ref "IC1") (pin "47") (pinfunction "VCAP2_47") (pintype "power_in"))
    )
    (net (code "59") (name "Net-(C4-1)") (class "Default")
      (node (ref "C4") (pin "P$1") (pinfunction "1_P$1") (pintype "passive"))
      (node (ref "C5") (pin "P$1") (pinfunction "1_P$1") (pintype "passive"))
      (node (ref "D1") (pin "3") (pinfunction "P$3_3") (pintype "output"))
      (node (ref "U1") (pin "1") (pinfunction "VIN_1") (pintype "power_in"))
      (node (ref "U1") (pin "3") (pinfunction "EN_3") (pintype "input"))
    )
    (net (code "60") (name "Net-(C6-1)") (class "Default")
      (node (ref "C6") (pin "P$1") (pinfunction "1_P$1") (pintype "passive"))
      (node (ref "U1") (pin "4") (pinfunction "NR_4") (pintype "input"))
    )
    (net (code "61") (name "Net-(C512-1)") (class "Default")
      (node (ref "C512") (pin "P$1") (pinfunction "1_P$1") (pintype "passive"))
      (node (ref "U505") (pin "10") (pinfunction "REGOUT_10") (pintype "bidirectional"))
    )
    (net (code "62") (name "Net-(C515-1)") (class "Default")
      (node (ref "C515") (pin "P$1") (pinfunction "1_P$1") (pintype "passive"))
      (node (ref "U505") (pin "20") (pinfunction "CPOUT_20") (pintype "bidirectional"))
    )
    (net (code "63") (name "Net-(IC1A-OSC_IN)") (class "Default")
      (node (ref "IC1") (pin "5") (pinfunction "OSC_IN_5") (pintype "bidirectional"))
      (node (ref "Q1") (pin "3") (pinfunction "3_3") (pintype "passive"))
    )
    (net (code "64") (name "Net-(IC1A-OSC_OUT)") (class "Default")
      (node (ref "IC1") (pin "6") (pinfunction "OSC_OUT_6") (pintype "bidirectional"))
      (node (ref "Q1") (pin "1") (pinfunction "1_1") (pintype "passive"))
    )
    (net (code "65") (name "Net-(R4-2)") (class "Default")
      (node (ref "LED2") (pin "A") (pinfunction "A_A") (pintype "passive"))
      (node (ref "R4") (pin "P$2") (pinfunction "2_P$2") (pintype "passive"))
    )
    (net (code "66") (name "Net-(R6-1)") (class "Default")
      (node (ref "R6") (pin "P$1") (pinfunction "1_P$1") (pintype "passive"))
      (node (ref "X1") (pin "4") (pinfunction "S_4") (pintype "passive"))
    )
    (net (code "67") (name "Net-(R7-1)") (class "Default")
      (node (ref "R7") (pin "P$1") (pinfunction "1_P$1") (pintype "passive"))
      (node (ref "X1") (pin "3") (pinfunction "S_3") (pintype "passive"))
    )
    (net (code "68") (name "Net-(R13-1)") (class "Default")
      (node (ref "R13") (pin "P$1") (pinfunction "1_P$1") (pintype "passive"))
      (node (ref "X1") (pin "2") (pinfunction "S_2") (pintype "passive"))
    )
    (net (code "69") (name "Net-(R15-2)") (class "Default")
      (node (ref "LED3") (pin "A") (pinfunction "A_A") (pintype "passive"))
      (node (ref "R15") (pin "P$2") (pinfunction "2_P$2") (pintype "passive"))
    )
    (net (code "70") (name "Net-(R801-2)") (class "Default")
      (node (ref "LED1") (pin "A") (pinfunction "A_A") (pintype "passive"))
      (node (ref "R801") (pin "P$2") (pinfunction "2_P$2") (pintype "passive"))
    )
    (net (code "71") (name "SPI_INT_MISO") (class "Default")
      (node (ref "IC1") (pin "22") (pinfunction "PA6_22") (pintype "bidirectional"))
      (node (ref "U505") (pin "9") (pinfunction "AD0/SDO_9") (pintype "bidirectional"))
    )
    (net (code "72") (name "SPI_INT_MOSI") (class "Default")
      (node (ref "IC1") (pin "23") (pinfunction "PA7_23") (pintype "bidirectional"))
      (node (ref "U505") (pin "24") (pinfunction "SDA/SDI_24") (pintype "bidirectional"))
    )
    (net (code "73") (name "SPI_INT_SCK") (class "Default")
      (node (ref "IC1") (pin "21") (pinfunction "PA5_21") (pintype "bidirectional"))
      (node (ref "U505") (pin "23") (pinfunction "SCL/SCLK_23") (pintype "bidirectional"))
    )
    (net (code "74") (name "VDD_3V3_SENSORS") (class "Default")
      (node (ref "C508") (pin "P$1") (pinfunction "1_P$1") (pintype "passive"))
      (node (ref "C513") (pin "P$1") (pinfunction "1_P$1") (pintype "passive"))
      (node (ref "C514") (pin "P$1") (pinfunction "1_P$1") (pintype "passive"))
      (node (ref "R5") (pin "2") (pinfunction "2_2") (pintype "passive"))
      (node (ref "U505") (pin "13") (pinfunction "VDD_13") (pintype "bidirectional"))
      (node (ref "U506") (pin "1") (pinfunction "VDD_1") (pintype "bidirectional"))
      (node (ref "U506") (pin "2") (pinfunction "PS_2") (pintype "bidirectional"))
    )
    (net (code "75") (name "unconnected-(IC1A-PB2-Pad28)") (class "Default")
      (node (ref "IC1") (pin "28") (pinfunction "PB2_28") (pintype "bidirectional"))
    )
    (net (code "76") (name "unconnected-(IC1A-PC13-Pad2)") (class "Default")
      (node (ref "IC1") (pin "2") (pinfunction "PC13_2") (pintype "bidirectional"))
    )
    (net (code "77") (name "unconnected-(IC1A-PC14-Pad3)") (class "Default")
      (node (ref "IC1") (pin "3") (pinfunction "PC14_3") (pintype "bidirectional"))
    )
    (net (code "78") (name "unconnected-(IC1A-PC15-Pad4)") (class "Default")
      (node (ref "IC1") (pin "4") (pinfunction "PC15_4") (pintype "bidirectional"))
    )
    (net (code "79") (name "unconnected-(J1-Pad4)") (class "Default")
      (node (ref "J1") (pin "4") (pinfunction "4_4") (pintype "input"))
    )
    (net (code "80") (name "unconnected-(U505-AUX_CL-Pad7)") (class "Default")
      (node (ref "U505") (pin "7") (pinfunction "AUX_CL_7") (pintype "bidirectional"))
    )
    (net (code "81") (name "unconnected-(U505-AUX_DA-Pad6)") (class "Default")
      (node (ref "U505") (pin "6") (pinfunction "AUX_DA_6") (pintype "bidirectional"))
    )
    (net (code "82") (name "unconnected-(U505-CLKOUT-Pad22)") (class "Default")
      (node (ref "U505") (pin "22") (pinfunction "CLKOUT_22") (pintype "bidirectional"))
    )
    (net (code "83") (name "unconnected-(U505-FSYNC-Pad11)") (class "Default")
      (node (ref "U505") (pin "11") (pinfunction "FSYNC_11") (pintype "bidirectional"))
    )
    (net (code "84") (name "unconnected-(U505-NC1-Pad2)") (class "Default")
      (node (ref "U505") (pin "2") (pinfunction "NC1_2") (pintype "bidirectional"))
    )
    (net (code "85") (name "unconnected-(U505-NC2-Pad3)") (class "Default")
      (node (ref "U505") (pin "3") (pinfunction "NC2_3") (pintype "bidirectional"))
    )
    (net (code "86") (name "unconnected-(U505-NC3-Pad4)") (class "Default")
      (node (ref "U505") (pin "4") (pinfunction "NC3_4") (pintype "bidirectional"))
    )
    (net (code "87") (name "unconnected-(U505-NC4-Pad5)") (class "Default")
      (node (ref "U505") (pin "5") (pinfunction "NC4_5") (pintype "bidirectional"))
    )
    (net (code "88") (name "unconnected-(U505-NC5-Pad14)") (class "Default")
      (node (ref "U505") (pin "14") (pinfunction "NC5_14") (pintype "bidirectional"))
    )
    (net (code "89") (name "unconnected-(U505-NC6-Pad15)") (class "Default")
      (node (ref "U505") (pin "15") (pinfunction "NC6_15") (pintype "bidirectional"))
    )
    (net (code "90") (name "unconnected-(U505-NC7-Pad16)") (class "Default")
      (node (ref "U505") (pin "16") (pinfunction "NC7_16") (pintype "bidirectional"))
    )
    (net (code "91") (name "unconnected-(U505-NC8-Pad17)") (class "Default")
      (node (ref "U505") (pin "17") (pinfunction "NC8_17") (pintype "bidirectional"))
    )
    (net (code "92") (name "unconnected-(U505-RESV1-Pad19)") (class "Default")
      (node (ref "U505") (pin "19") (pinfunction "RESV1_19") (pintype "bidirectional"))
    )
    (net (code "93") (name "unconnected-(U505-RESV2-Pad21)") (class "Default")
      (node (ref "U505") (pin "21") (pinfunction "RESV2_21") (pintype "bidirectional"))
    )
    (net (code "94") (name "unconnected-(U506-CSB1-Pad4)") (class "Default")
      (node (ref "U506") (pin "4") (pinfunction "CSB1_4") (pintype "bidirectional"))
    )
    (net (code "95") (name "unconnected-(U506-CSB2-Pad5)") (class "Default")
      (node (ref "U506") (pin "5") (pinfunction "CSB2_5") (pintype "bidirectional"))
    )
    (net (code "96") (name "unconnected-(U506-SDO-Pad6)") (class "Default")
      (node (ref "U506") (pin "6") (pinfunction "SDO_6") (pintype "bidirectional"))
    )
  )
)
